# ASI-CANOpen.net
KiCad netlist of a schematic drawn in Altium Designer
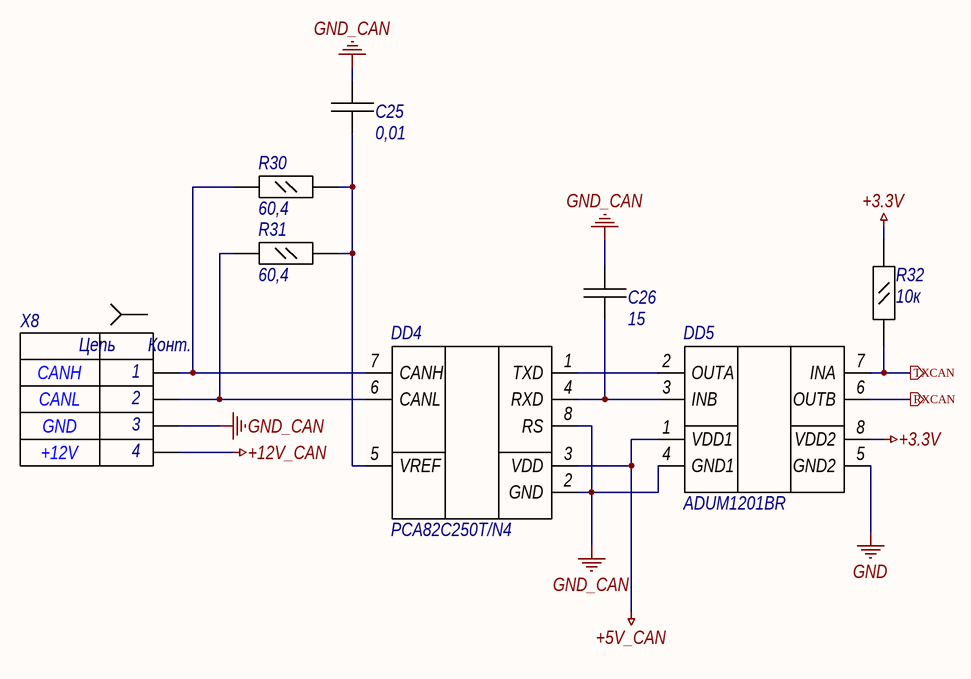
[diagram p0: ASI-CANOpen.SchDoc]

(export (version "E")
  (design (tool "Eeschema 10.0.6"))
  (components
    (comp (ref "C25")
      (value "0,01")
      (footprint "0805")
      (description "Конденсатор")
      (fields (field (name "MANUFACTURER") "YAGEO"))
      (libsource (lib "DX_test_lib2") (part "CC0805"))
    )
    (comp (ref "C26")
      (value "15")
      (footprint "0805")
      (description "Конденсатор")
      (fields (field (name "MANUFACTURER") "YAGEO"))
      (libsource (lib "DX_test_lib2") (part "CC0805"))
    )
    (comp (ref "DD4")
      (value "PCA82C250T/N4")
      (footprint "SO-8")
      (description "Интерфейс физического уровня CAN")
      (fields (field (name "MANUFACTURER") "NXP"))
      (libsource (lib "Micro_Digital") (part "PCA82C250T"))
    )
    (comp (ref "DD5")
      (value "ADUM1201BR")
      (footprint "SO-8")
      (description "Изолятор цифрового сигнала")
      (fields (field (name "MANUFACTURER") "Analog Dev."))
      (libsource (lib "Micro_Digital") (part "ADUM1201"))
    )
    (comp (ref "R30")
      (value "60,4")
      (footprint "0805")
      (description "Резистор общего назначения 5%")
      (fields (field (name "MANUFACTURER") "YAGEO"))
      (libsource (lib "DX_test_lib2") (part "RC0805JR"))
    )
    (comp (ref "R31")
      (value "60,4")
      (footprint "0805")
      (description "Резистор общего назначения 5%")
      (fields (field (name "MANUFACTURER") "YAGEO"))
      (libsource (lib "DX_test_lib2") (part "RC0805JR"))
    )
    (comp (ref "R32")
      (value "10к")
      (footprint "0805")
      (description "Резистор общего назначения 5%")
      (fields (field (name "MANUFACTURER") "YAGEO"))
      (libsource (lib "DX_test_lib2") (part "RC0805JR"))
    )
    (comp (ref "X8")
      (value "TJ3-4P4C")
      (footprint "TJ3-4P4C")
      (description "Разъем, гнездо на плату, прямой")
      (libsource (lib "Connectors_TJ") (part "TJ3-4P4C"))
    )
  )
  (nets
    (net (code "1") (name "+3.3V") (class "Default")
      (node (ref "DD5") (pin "8") (pinfunction "VDD2_8") (pintype "passive"))
      (node (ref "R32") (pin "2") (pinfunction "2_2") (pintype "passive"))
    )
    (net (code "2") (name "+5V_CAN") (class "Default")
      (node (ref "DD4") (pin "3") (pinfunction "VDD_3") (pintype "passive"))
      (node (ref "DD5") (pin "1") (pinfunction "VDD1_1") (pintype "passive"))
    )
    (net (code "3") (name "+12V_CAN") (class "Default")
      (node (ref "X8") (pin "4") (pinfunction "4_4") (pintype "passive"))
    )
    (net (code "4") (name "/RXCAN") (class "Default")
      (node (ref "DD5") (pin "6") (pinfunction "OUTB_6") (pintype "passive"))
    )
    (net (code "5") (name "/TXCAN") (class "Default")
      (node (ref "DD5") (pin "7") (pinfunction "INA_7") (pintype "passive"))
      (node (ref "R32") (pin "1") (pinfunction "1_1") (pintype "passive"))
    )
    (net (code "6") (name "GND") (class "Default")
      (node (ref "DD5") (pin "5") (pinfunction "GND2_5") (pintype "passive"))
    )
    (net (code "7") (name "GND_CAN") (class "Default")
      (node (ref "C25") (pin "2") (pinfunction "2_2") (pintype "passive"))
      (node (ref "C26") (pin "2") (pinfunction "2_2") (pintype "passive"))
      (node (ref "DD4") (pin "2") (pinfunction "GND_2") (pintype "passive"))
      (node (ref "DD4") (pin "8") (pinfunction "RS_8") (pintype "passive"))
      (node (ref "DD5") (pin "4") (pinfunction "GND1_4") (pintype "passive"))
      (node (ref "X8") (pin "3") (pinfunction "3_3") (pintype "passive"))
    )
    (net (code "8") (name "Net-(DD4-CANH)") (class "Default")
      (node (ref "DD4") (pin "7") (pinfunction "CANH_7") (pintype "passive"))
      (node (ref "R30") (pin "1") (pinfunction "1_1") (pintype "passive"))
      (node (ref "X8") (pin "1") (pinfunction "1_1") (pintype "passive"))
    )
    (net (code "9") (name "Net-(DD4-CANL)") (class "Default")
      (node (ref "DD4") (pin "6") (pinfunction "CANL_6") (pintype "passive"))
      (node (ref "R31") (pin "1") (pinfunction "1_1") (pintype "passive"))
      (node (ref "X8") (pin "2") (pinfunction "2_2") (pintype "passive"))
    )
    (net (code "10") (name "Net-(DD4-RXD)") (class "Default")
      (node (ref "C26") (pin "1") (pinfunction "1_1") (pintype "passive"))
      (node (ref "DD4") (pin "4") (pinfunction "RXD_4") (pintype "passive"))
      (node (ref "DD5") (pin "3") (pinfunction "INB_3") (pintype "passive"))
    )
    (net (code "11") (name "Net-(DD4-TXD)") (class "Default")
      (node (ref "DD4") (pin "1") (pinfunction "TXD_1") (pintype "passive"))
      (node (ref "DD5") (pin "2") (pinfunction "OUTA_2") (pintype "passive"))
    )
    (net (code "12") (name "Net-(DD4-VREF)") (class "Default")
      (node (ref "C25") (pin "1") (pinfunction "1_1") (pintype "passive"))
      (node (ref "DD4") (pin "5") (pinfunction "VREF_5") (pintype "passive"))
      (node (ref "R30") (pin "2") (pinfunction "2_2") (pintype "passive"))
      (node (ref "R31") (pin "2") (pinfunction "2_2") (pintype "passive"))
    )
  )
)
